# Drawing_binary_decimal_converter.net
KiCad netlist of a schematic drawn in EAGLE
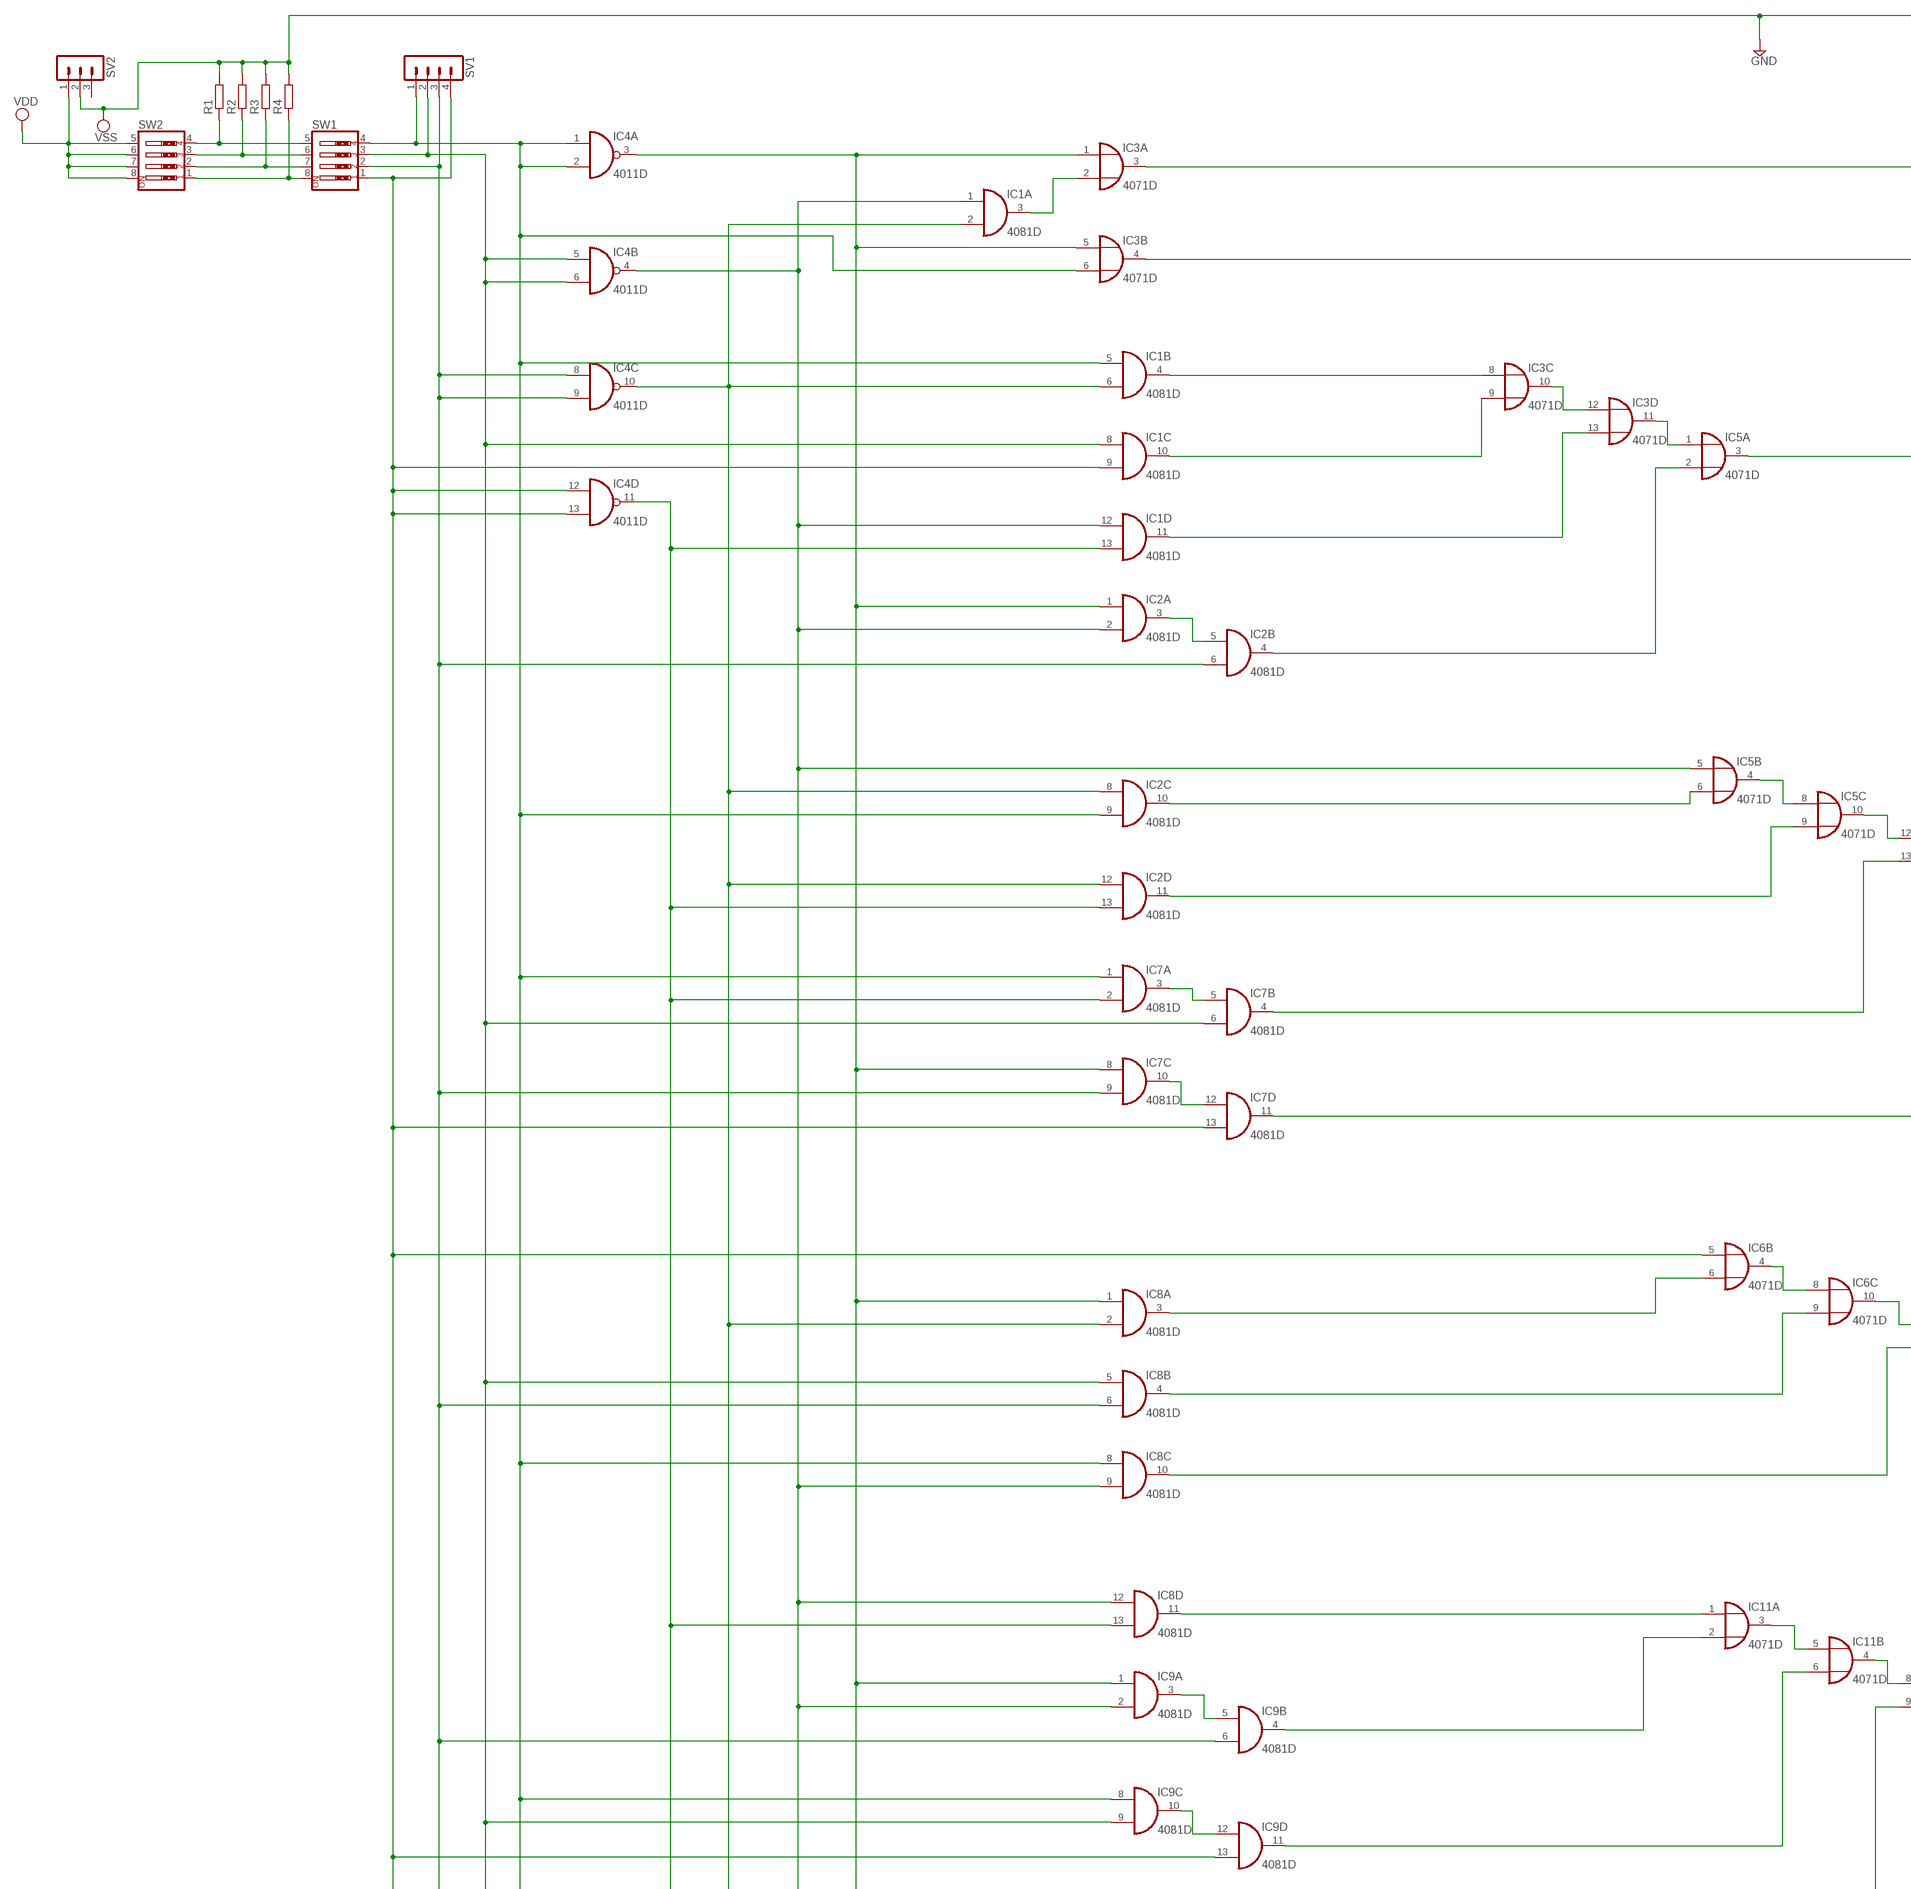
[diagram p0: schematic, sheet 1, part 1 of 3]
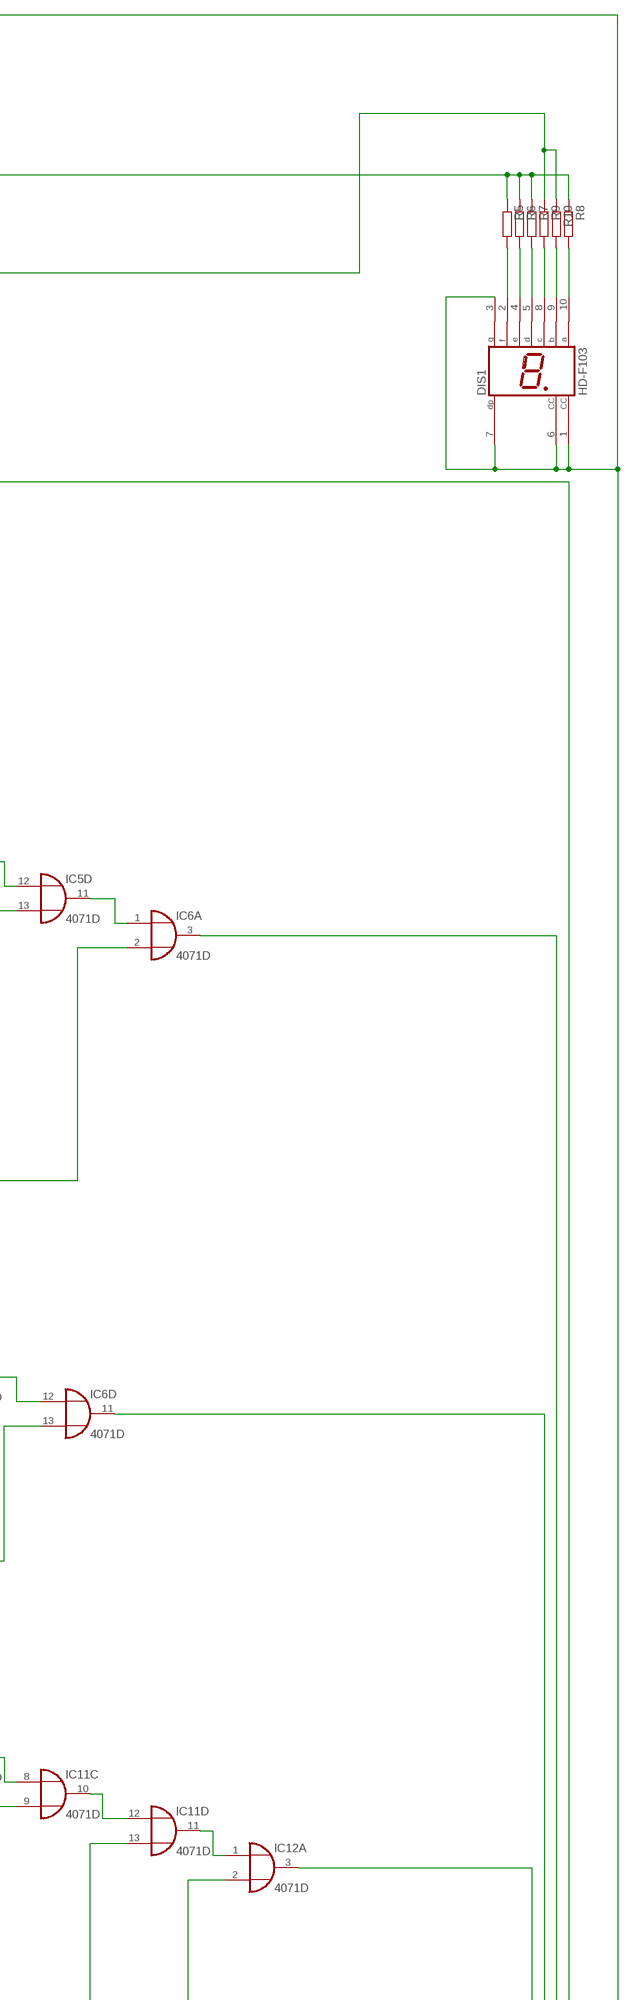
[diagram p1: schematic, sheet 1, part 2 of 3]
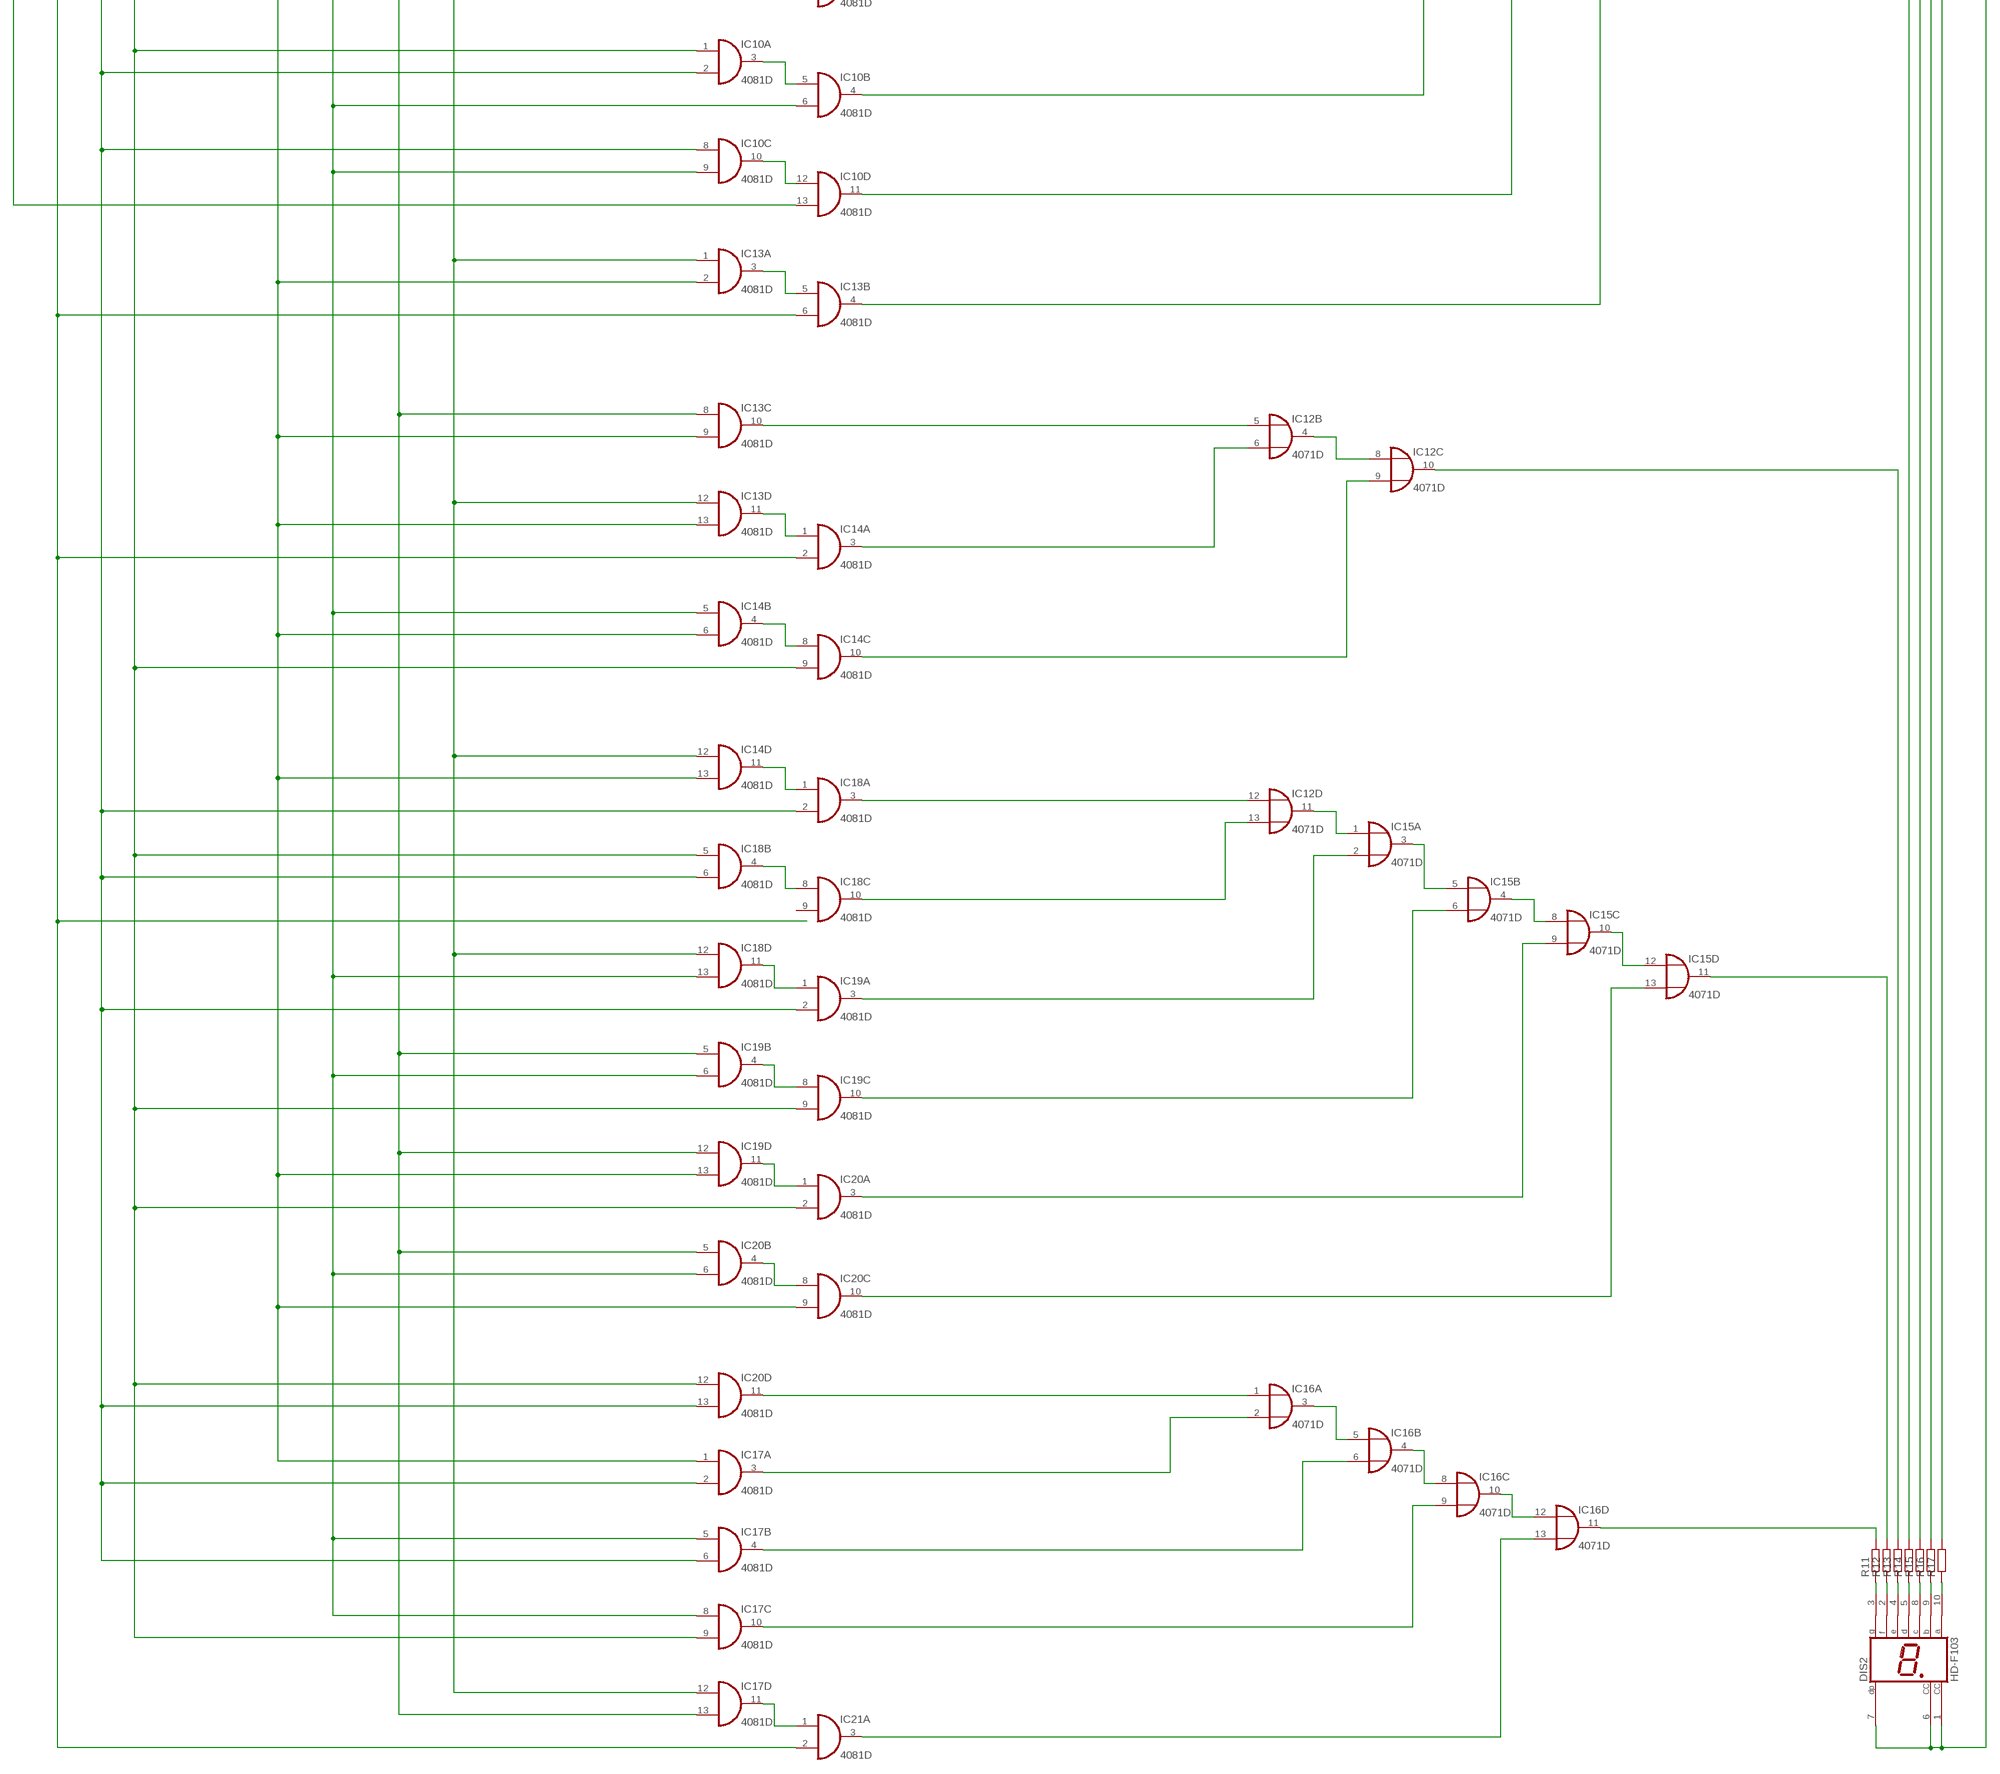
[diagram p2: schematic, sheet 1, part 3 of 3]

(export (version "E")
  (design (tool "Eeschema 10.0.6"))
  (components
    (comp (ref "DIS1")
      (value "HD-F103")
      (footprint "eagle-import:HDSP-E")
      (libsource (lib "eagle-import") (part "HD-F103"))
    )
    (comp (ref "DIS2")
      (value "HD-F103")
      (footprint "eagle-import:HDSP-E")
      (libsource (lib "eagle-import") (part "HD-F103"))
    )
    (comp (ref "IC1")
      (value "4081D")
      (footprint "eagle-import:SO14")
      (libsource (lib "eagle-import") (part "4081D"))
    )
    (comp (ref "IC2")
      (value "4081D")
      (footprint "eagle-import:SO14")
      (libsource (lib "eagle-import") (part "4081D"))
    )
    (comp (ref "IC3")
      (value "4071D")
      (footprint "eagle-import:SO14")
      (libsource (lib "eagle-import") (part "4071D"))
    )
    (comp (ref "IC4")
      (value "4011D")
      (footprint "eagle-import:SO14")
      (libsource (lib "eagle-import") (part "4011D"))
    )
    (comp (ref "IC5")
      (value "4071D")
      (footprint "eagle-import:SO14")
      (libsource (lib "eagle-import") (part "4071D"))
    )
    (comp (ref "IC6")
      (value "4071D")
      (footprint "eagle-import:SO14")
      (libsource (lib "eagle-import") (part "4071D"))
    )
    (comp (ref "IC7")
      (value "4081D")
      (footprint "eagle-import:SO14")
      (libsource (lib "eagle-import") (part "4081D"))
    )
    (comp (ref "IC8")
      (value "4081D")
      (footprint "eagle-import:SO14")
      (libsource (lib "eagle-import") (part "4081D"))
    )
    (comp (ref "IC9")
      (value "4081D")
      (footprint "eagle-import:SO14")
      (libsource (lib "eagle-import") (part "4081D"))
    )
    (comp (ref "IC10")
      (value "4081D")
      (footprint "eagle-import:SO14")
      (libsource (lib "eagle-import") (part "4081D"))
    )
    (comp (ref "IC11")
      (value "4071D")
      (footprint "eagle-import:SO14")
      (libsource (lib "eagle-import") (part "4071D"))
    )
    (comp (ref "IC12")
      (value "4071D")
      (footprint "eagle-import:SO14")
      (libsource (lib "eagle-import") (part "4071D"))
    )
    (comp (ref "IC13")
      (value "4081D")
      (footprint "eagle-import:SO14")
      (libsource (lib "eagle-import") (part "4081D"))
    )
    (comp (ref "IC14")
      (value "4081D")
      (footprint "eagle-import:SO14")
      (libsource (lib "eagle-import") (part "4081D"))
    )
    (comp (ref "IC15")
      (value "4071D")
      (footprint "eagle-import:SO14")
      (libsource (lib "eagle-import") (part "4071D"))
    )
    (comp (ref "IC16")
      (value "4071D")
      (footprint "eagle-import:SO14")
      (libsource (lib "eagle-import") (part "4071D"))
    )
    (comp (ref "IC17")
      (value "4081D")
      (footprint "eagle-import:SO14")
      (libsource (lib "eagle-import") (part "4081D"))
    )
    (comp (ref "IC18")
      (value "4081D")
      (footprint "eagle-import:SO14")
      (libsource (lib "eagle-import") (part "4081D"))
    )
    (comp (ref "IC19")
      (value "4081D")
      (footprint "eagle-import:SO14")
      (libsource (lib "eagle-import") (part "4081D"))
    )
    (comp (ref "IC20")
      (value "4081D")
      (footprint "eagle-import:SO14")
      (libsource (lib "eagle-import") (part "4081D"))
    )
    (comp (ref "IC21")
      (value "4081D")
      (footprint "eagle-import:SO14")
      (libsource (lib "eagle-import") (part "4081D"))
    )
    (comp (ref "R1")
      (value "R-EU_R1206")
      (footprint "eagle-import:R1206")
      (libsource (lib "eagle-import") (part "R-EU_R1206"))
    )
    (comp (ref "R2")
      (value "R-EU_R1206")
      (footprint "eagle-import:R1206")
      (libsource (lib "eagle-import") (part "R-EU_R1206"))
    )
    (comp (ref "R3")
      (value "R-EU_R1206")
      (footprint "eagle-import:R1206")
      (libsource (lib "eagle-import") (part "R-EU_R1206"))
    )
    (comp (ref "R4")
      (value "R-EU_R1206")
      (footprint "eagle-import:R1206")
      (libsource (lib "eagle-import") (part "R-EU_R1206"))
    )
    (comp (ref "R5")
      (value "R-EU_R1206")
      (footprint "eagle-import:R1206")
      (libsource (lib "eagle-import") (part "R-EU_R1206"))
    )
    (comp (ref "R6")
      (value "R-EU_R1206")
      (footprint "eagle-import:R1206")
      (libsource (lib "eagle-import") (part "R-EU_R1206"))
    )
    (comp (ref "R7")
      (value "R-EU_R1206")
      (footprint "eagle-import:R1206")
      (libsource (lib "eagle-import") (part "R-EU_R1206"))
    )
    (comp (ref "R8")
      (value "R-EU_R1206")
      (footprint "eagle-import:R1206")
      (libsource (lib "eagle-import") (part "R-EU_R1206"))
    )
    (comp (ref "R9")
      (value "R-EU_R1206")
      (footprint "eagle-import:R1206")
      (libsource (lib "eagle-import") (part "R-EU_R1206"))
    )
    (comp (ref "R10")
      (value "R-EU_R1206")
      (footprint "eagle-import:R1206")
      (libsource (lib "eagle-import") (part "R-EU_R1206"))
    )
    (comp (ref "R11")
      (value "R-EU_R1206")
      (footprint "eagle-import:R1206")
      (libsource (lib "eagle-import") (part "R-EU_R1206"))
    )
    (comp (ref "R12")
      (value "R-EU_R1206")
      (footprint "eagle-import:R1206")
      (libsource (lib "eagle-import") (part "R-EU_R1206"))
    )
    (comp (ref "R13")
      (value "R-EU_R1206")
      (footprint "eagle-import:R1206")
      (libsource (lib "eagle-import") (part "R-EU_R1206"))
    )
    (comp (ref "R14")
      (value "R-EU_R1206")
      (footprint "eagle-import:R1206")
      (libsource (lib "eagle-import") (part "R-EU_R1206"))
    )
    (comp (ref "R15")
      (value "R-EU_R1206")
      (footprint "eagle-import:R1206")
      (libsource (lib "eagle-import") (part "R-EU_R1206"))
    )
    (comp (ref "R16")
      (value "R-EU_R1206")
      (footprint "eagle-import:R1206")
      (libsource (lib "eagle-import") (part "R-EU_R1206"))
    )
    (comp (ref "R17")
      (value "R-EU_R1206")
      (footprint "eagle-import:R1206")
      (libsource (lib "eagle-import") (part "R-EU_R1206"))
    )
    (comp (ref "SV1")
      (value "MA04-1")
      (footprint "eagle-import:MA04-1")
      (libsource (lib "eagle-import") (part "MA04-1"))
    )
    (comp (ref "SV2")
      (value "MA03-1")
      (footprint "eagle-import:MA03-1")
      (libsource (lib "eagle-import") (part "MA03-1"))
    )
    (comp (ref "SW1")
      (value "SW_DIP-4")
      (footprint "eagle-import:EDG-04")
      (libsource (lib "eagle-import") (part "SW_DIP-4"))
    )
    (comp (ref "SW2")
      (value "SW_DIP-4")
      (footprint "eagle-import:EDG-04")
      (libsource (lib "eagle-import") (part "SW_DIP-4"))
    )
  )
  (nets
    (net (code "1") (name "GND") (class "Default")
      (node (ref "DIS1") (pin "1") (pinfunction "CC_1") (pintype "passive"))
      (node (ref "DIS1") (pin "3") (pinfunction "G_3") (pintype "passive"))
      (node (ref "DIS1") (pin "6") (pinfunction "CC_6") (pintype "passive"))
      (node (ref "DIS1") (pin "7") (pinfunction "DP_7") (pintype "passive"))
      (node (ref "DIS2") (pin "1") (pinfunction "CC_1") (pintype "passive"))
      (node (ref "DIS2") (pin "6") (pinfunction "CC_6") (pintype "passive"))
      (node (ref "DIS2") (pin "7") (pinfunction "DP_7") (pintype "passive"))
      (node (ref "R1") (pin "2") (pinfunction "2_2") (pintype "passive"))
      (node (ref "R2") (pin "2") (pinfunction "2_2") (pintype "passive"))
      (node (ref "R3") (pin "2") (pinfunction "2_2") (pintype "passive"))
      (node (ref "R4") (pin "2") (pinfunction "2_2") (pintype "passive"))
      (node (ref "SV2") (pin "2") (pinfunction "2_2") (pintype "passive"))
    )
    (net (code "2") (name "Net-(DIS1-A)") (class "Default")
      (node (ref "DIS1") (pin "10") (pinfunction "A_10") (pintype "passive"))
      (node (ref "R8") (pin "2") (pinfunction "2_2") (pintype "passive"))
    )
    (net (code "3") (name "Net-(DIS1-B)") (class "Default")
      (node (ref "DIS1") (pin "9") (pinfunction "B_9") (pintype "passive"))
      (node (ref "R10") (pin "2") (pinfunction "2_2") (pintype "passive"))
    )
    (net (code "4") (name "Net-(DIS1-C)") (class "Default")
      (node (ref "DIS1") (pin "8") (pinfunction "C_8") (pintype "passive"))
      (node (ref "R9") (pin "2") (pinfunction "2_2") (pintype "passive"))
    )
    (net (code "5") (name "Net-(DIS1-D)") (class "Default")
      (node (ref "DIS1") (pin "5") (pinfunction "D_5") (pintype "passive"))
      (node (ref "R7") (pin "2") (pinfunction "2_2") (pintype "passive"))
    )
    (net (code "6") (name "Net-(DIS1-E)") (class "Default")
      (node (ref "DIS1") (pin "4") (pinfunction "E_4") (pintype "passive"))
      (node (ref "R6") (pin "2") (pinfunction "2_2") (pintype "passive"))
    )
    (net (code "7") (name "Net-(DIS1-F)") (class "Default")
      (node (ref "DIS1") (pin "2") (pinfunction "F_2") (pintype "passive"))
      (node (ref "R5") (pin "2") (pinfunction "2_2") (pintype "passive"))
    )
    (net (code "8") (name "Net-(DIS2-A)") (class "Default")
      (node (ref "DIS2") (pin "10") (pinfunction "A_10") (pintype "passive"))
      (node (ref "R17") (pin "1") (pinfunction "1_1") (pintype "passive"))
    )
    (net (code "9") (name "Net-(DIS2-B)") (class "Default")
      (node (ref "DIS2") (pin "9") (pinfunction "B_9") (pintype "passive"))
      (node (ref "R16") (pin "1") (pinfunction "1_1") (pintype "passive"))
    )
    (net (code "10") (name "Net-(DIS2-C)") (class "Default")
      (node (ref "DIS2") (pin "8") (pinfunction "C_8") (pintype "passive"))
      (node (ref "R15") (pin "1") (pinfunction "1_1") (pintype "passive"))
    )
    (net (code "11") (name "Net-(DIS2-D)") (class "Default")
      (node (ref "DIS2") (pin "5") (pinfunction "D_5") (pintype "passive"))
      (node (ref "R14") (pin "1") (pinfunction "1_1") (pintype "passive"))
    )
    (net (code "12") (name "Net-(DIS2-E)") (class "Default")
      (node (ref "DIS2") (pin "4") (pinfunction "E_4") (pintype "passive"))
      (node (ref "R13") (pin "1") (pinfunction "1_1") (pintype "passive"))
    )
    (net (code "13") (name "Net-(DIS2-F)") (class "Default")
      (node (ref "DIS2") (pin "2") (pinfunction "F_2") (pintype "passive"))
      (node (ref "R12") (pin "1") (pinfunction "1_1") (pintype "passive"))
    )
    (net (code "14") (name "Net-(DIS2-G)") (class "Default")
      (node (ref "DIS2") (pin "3") (pinfunction "G_3") (pintype "passive"))
      (node (ref "R11") (pin "1") (pinfunction "1_1") (pintype "passive"))
    )
    (net (code "15") (name "Net-(IC1A-O)") (class "Default")
      (node (ref "IC1") (pin "3") (pinfunction "O_3") (pintype "output"))
      (node (ref "IC3") (pin "2") (pinfunction "I1_2") (pintype "input"))
    )
    (net (code "16") (name "Net-(IC1B-O)") (class "Default")
      (node (ref "IC1") (pin "4") (pinfunction "O_4") (pintype "output"))
      (node (ref "IC3") (pin "8") (pinfunction "I0_8") (pintype "input"))
    )
    (net (code "17") (name "Net-(IC1C-O)") (class "Default")
      (node (ref "IC1") (pin "10") (pinfunction "O_10") (pintype "output"))
      (node (ref "IC3") (pin "9") (pinfunction "I1_9") (pintype "input"))
    )
    (net (code "18") (name "Net-(IC1D-O)") (class "Default")
      (node (ref "IC1") (pin "11") (pinfunction "O_11") (pintype "output"))
      (node (ref "IC3") (pin "13") (pinfunction "I1_13") (pintype "input"))
    )
    (net (code "19") (name "Net-(IC2A-O)") (class "Default")
      (node (ref "IC2") (pin "3") (pinfunction "O_3") (pintype "output"))
      (node (ref "IC2") (pin "5") (pinfunction "I0_5") (pintype "input"))
    )
    (net (code "20") (name "Net-(IC2B-O)") (class "Default")
      (node (ref "IC2") (pin "4") (pinfunction "O_4") (pintype "output"))
      (node (ref "IC5") (pin "2") (pinfunction "I1_2") (pintype "input"))
    )
    (net (code "21") (name "Net-(IC2C-O)") (class "Default")
      (node (ref "IC2") (pin "10") (pinfunction "O_10") (pintype "output"))
      (node (ref "IC5") (pin "6") (pinfunction "I1_6") (pintype "input"))
    )
    (net (code "22") (name "Net-(IC2D-O)") (class "Default")
      (node (ref "IC2") (pin "11") (pinfunction "O_11") (pintype "output"))
      (node (ref "IC5") (pin "9") (pinfunction "I1_9") (pintype "input"))
    )
    (net (code "23") (name "Net-(IC3A-O)") (class "Default")
      (node (ref "IC3") (pin "3") (pinfunction "O_3") (pintype "output"))
      (node (ref "R5") (pin "1") (pinfunction "1_1") (pintype "passive"))
      (node (ref "R6") (pin "1") (pinfunction "1_1") (pintype "passive"))
      (node (ref "R7") (pin "1") (pinfunction "1_1") (pintype "passive"))
      (node (ref "R8") (pin "1") (pinfunction "1_1") (pintype "passive"))
    )
    (net (code "24") (name "Net-(IC3B-O)") (class "Default")
      (node (ref "IC3") (pin "4") (pinfunction "O_4") (pintype "output"))
      (node (ref "R10") (pin "1") (pinfunction "1_1") (pintype "passive"))
      (node (ref "R9") (pin "1") (pinfunction "1_1") (pintype "passive"))
    )
    (net (code "25") (name "Net-(IC3C-O)") (class "Default")
      (node (ref "IC3") (pin "10") (pinfunction "O_10") (pintype "output"))
      (node (ref "IC3") (pin "12") (pinfunction "I0_12") (pintype "input"))
    )
    (net (code "26") (name "Net-(IC3D-O)") (class "Default")
      (node (ref "IC3") (pin "11") (pinfunction "O_11") (pintype "output"))
      (node (ref "IC5") (pin "1") (pinfunction "I0_1") (pintype "input"))
    )
    (net (code "27") (name "Net-(IC5A-O)") (class "Default")
      (node (ref "IC5") (pin "3") (pinfunction "O_3") (pintype "output"))
      (node (ref "R17") (pin "2") (pinfunction "2_2") (pintype "passive"))
    )
    (net (code "28") (name "Net-(IC5B-O)") (class "Default")
      (node (ref "IC5") (pin "4") (pinfunction "O_4") (pintype "output"))
      (node (ref "IC5") (pin "8") (pinfunction "I0_8") (pintype "input"))
    )
    (net (code "29") (name "Net-(IC5C-O)") (class "Default")
      (node (ref "IC5") (pin "10") (pinfunction "O_10") (pintype "output"))
      (node (ref "IC5") (pin "12") (pinfunction "I0_12") (pintype "input"))
    )
    (net (code "30") (name "Net-(IC5D-I1)") (class "Default")
      (node (ref "IC5") (pin "13") (pinfunction "I1_13") (pintype "input"))
      (node (ref "IC7") (pin "4") (pinfunction "O_4") (pintype "output"))
    )
    (net (code "31") (name "Net-(IC5D-O)") (class "Default")
      (node (ref "IC5") (pin "11") (pinfunction "O_11") (pintype "output"))
      (node (ref "IC6") (pin "1") (pinfunction "I0_1") (pintype "input"))
    )
    (net (code "32") (name "Net-(IC6A-I1)") (class "Default")
      (node (ref "IC6") (pin "2") (pinfunction "I1_2") (pintype "input"))
      (node (ref "IC7") (pin "11") (pinfunction "O_11") (pintype "output"))
    )
    (net (code "33") (name "Net-(IC6A-O)") (class "Default")
      (node (ref "IC6") (pin "3") (pinfunction "O_3") (pintype "output"))
      (node (ref "R16") (pin "2") (pinfunction "2_2") (pintype "passive"))
    )
    (net (code "34") (name "Net-(IC6B-I1)") (class "Default")
      (node (ref "IC6") (pin "6") (pinfunction "I1_6") (pintype "input"))
      (node (ref "IC8") (pin "3") (pinfunction "O_3") (pintype "output"))
    )
    (net (code "35") (name "Net-(IC6B-O)") (class "Default")
      (node (ref "IC6") (pin "4") (pinfunction "O_4") (pintype "output"))
      (node (ref "IC6") (pin "8") (pinfunction "I0_8") (pintype "input"))
    )
    (net (code "36") (name "Net-(IC6C-I1)") (class "Default")
      (node (ref "IC6") (pin "9") (pinfunction "I1_9") (pintype "input"))
      (node (ref "IC8") (pin "4") (pinfunction "O_4") (pintype "output"))
    )
    (net (code "37") (name "Net-(IC6C-O)") (class "Default")
      (node (ref "IC6") (pin "10") (pinfunction "O_10") (pintype "output"))
      (node (ref "IC6") (pin "12") (pinfunction "I0_12") (pintype "input"))
    )
    (net (code "38") (name "Net-(IC6D-I1)") (class "Default")
      (node (ref "IC6") (pin "13") (pinfunction "I1_13") (pintype "input"))
      (node (ref "IC8") (pin "10") (pinfunction "O_10") (pintype "output"))
    )
    (net (code "39") (name "Net-(IC6D-O)") (class "Default")
      (node (ref "IC6") (pin "11") (pinfunction "O_11") (pintype "output"))
      (node (ref "R15") (pin "2") (pinfunction "2_2") (pintype "passive"))
    )
    (net (code "40") (name "Net-(IC7A-O)") (class "Default")
      (node (ref "IC7") (pin "3") (pinfunction "O_3") (pintype "output"))
      (node (ref "IC7") (pin "5") (pinfunction "I0_5") (pintype "input"))
    )
    (net (code "41") (name "Net-(IC7C-O)") (class "Default")
      (node (ref "IC7") (pin "10") (pinfunction "O_10") (pintype "output"))
      (node (ref "IC7") (pin "12") (pinfunction "I0_12") (pintype "input"))
    )
    (net (code "42") (name "Net-(IC9A-O)") (class "Default")
      (node (ref "IC9") (pin "3") (pinfunction "O_3") (pintype "output"))
      (node (ref "IC9") (pin "5") (pinfunction "I0_5") (pintype "input"))
    )
    (net (code "43") (name "Net-(IC9C-O)") (class "Default")
      (node (ref "IC9") (pin "10") (pinfunction "O_10") (pintype "output"))
      (node (ref "IC9") (pin "12") (pinfunction "I0_12") (pintype "input"))
    )
    (net (code "44") (name "Net-(IC10A-I0)") (class "Default")
      (node (ref "IC1") (pin "5") (pinfunction "I0_5") (pintype "input"))
      (node (ref "IC10") (pin "1") (pinfunction "I0_1") (pintype "input"))
      (node (ref "IC14") (pin "9") (pinfunction "I1_9") (pintype "input"))
      (node (ref "IC17") (pin "9") (pinfunction "I1_9") (pintype "input"))
      (node (ref "IC18") (pin "5") (pinfunction "I0_5") (pintype "input"))
      (node (ref "IC19") (pin "9") (pinfunction "I1_9") (pintype "input"))
      (node (ref "IC2") (pin "9") (pinfunction "I1_9") (pintype "input"))
      (node (ref "IC20") (pin "12") (pinfunction "I0_12") (pintype "input"))
      (node (ref "IC20") (pin "2") (pinfunction "I1_2") (pintype "input"))
      (node (ref "IC3") (pin "6") (pinfunction "I1_6") (pintype "input"))
      (node (ref "IC4") (pin "1") (pinfunction "I0_1") (pintype "input"))
      (node (ref "IC4") (pin "2") (pinfunction "I1_2") (pintype "input"))
      (node (ref "IC7") (pin "1") (pinfunction "I0_1") (pintype "input"))
      (node (ref "IC8") (pin "8") (pinfunction "I0_8") (pintype "input"))
      (node (ref "IC9") (pin "8") (pinfunction "I0_8") (pintype "input"))
      (node (ref "SV1") (pin "1") (pinfunction "1_1") (pintype "passive"))
      (node (ref "SW1") (pin "4") (pinfunction "4_4") (pintype "passive"))
    )
    (net (code "45") (name "Net-(IC10A-I1)") (class "Default")
      (node (ref "IC1") (pin "8") (pinfunction "I0_8") (pintype "input"))
      (node (ref "IC10") (pin "2") (pinfunction "I1_2") (pintype "input"))
      (node (ref "IC10") (pin "8") (pinfunction "I0_8") (pintype "input"))
      (node (ref "IC17") (pin "2") (pinfunction "I1_2") (pintype "input"))
      (node (ref "IC17") (pin "6") (pinfunction "I1_6") (pintype "input"))
      (node (ref "IC18") (pin "2") (pinfunction "I1_2") (pintype "input"))
      (node (ref "IC18") (pin "6") (pinfunction "I1_6") (pintype "input"))
      (node (ref "IC19") (pin "2") (pinfunction "I1_2") (pintype "input"))
      (node (ref "IC20") (pin "13") (pinfunction "I1_13") (pintype "input"))
      (node (ref "IC4") (pin "5") (pinfunction "I0_5") (pintype "input"))
      (node (ref "IC4") (pin "6") (pinfunction "I1_6") (pintype "input"))
      (node (ref "IC7") (pin "6") (pinfunction "I1_6") (pintype "input"))
      (node (ref "IC8") (pin "5") (pinfunction "I0_5") (pintype "input"))
      (node (ref "IC9") (pin "9") (pinfunction "I1_9") (pintype "input"))
      (node (ref "SV1") (pin "2") (pinfunction "2_2") (pintype "passive"))
      (node (ref "SW1") (pin "3") (pinfunction "3_3") (pintype "passive"))
    )
    (net (code "46") (name "Net-(IC10A-O)") (class "Default")
      (node (ref "IC10") (pin "3") (pinfunction "O_3") (pintype "output"))
      (node (ref "IC10") (pin "5") (pinfunction "I0_5") (pintype "input"))
    )
    (net (code "47") (name "Net-(IC10B-I1)") (class "Default")
      (node (ref "IC1") (pin "2") (pinfunction "I1_2") (pintype "input"))
      (node (ref "IC1") (pin "6") (pinfunction "I1_6") (pintype "input"))
      (node (ref "IC10") (pin "6") (pinfunction "I1_6") (pintype "input"))
      (node (ref "IC10") (pin "9") (pinfunction "I1_9") (pintype "input"))
      (node (ref "IC14") (pin "5") (pinfunction "I0_5") (pintype "input"))
      (node (ref "IC17") (pin "5") (pinfunction "I0_5") (pintype "input"))
      (node (ref "IC17") (pin "8") (pinfunction "I0_8") (pintype "input"))
      (node (ref "IC18") (pin "13") (pinfunction "I1_13") (pintype "input"))
      (node (ref "IC19") (pin "6") (pinfunction "I1_6") (pintype "input"))
      (node (ref "IC2") (pin "12") (pinfunction "I0_12") (pintype "input"))
      (node (ref "IC2") (pin "8") (pinfunction "I0_8") (pintype "input"))
      (node (ref "IC20") (pin "6") (pinfunction "I1_6") (pintype "input"))
      (node (ref "IC4") (pin "10") (pinfunction "O_10") (pintype "output"))
      (node (ref "IC8") (pin "2") (pinfunction "I1_2") (pintype "input"))
    )
    (net (code "48") (name "Net-(IC10B-O)") (class "Default")
      (node (ref "IC10") (pin "4") (pinfunction "O_4") (pintype "output"))
      (node (ref "IC11") (pin "9") (pinfunction "I1_9") (pintype "input"))
    )
    (net (code "49") (name "Net-(IC10C-O)") (class "Default")
      (node (ref "IC10") (pin "10") (pinfunction "O_10") (pintype "output"))
      (node (ref "IC10") (pin "12") (pinfunction "I0_12") (pintype "input"))
    )
    (net (code "50") (name "Net-(IC10D-I1)") (class "Default")
      (node (ref "IC1") (pin "9") (pinfunction "I1_9") (pintype "input"))
      (node (ref "IC10") (pin "13") (pinfunction "I1_13") (pintype "input"))
      (node (ref "IC4") (pin "12") (pinfunction "I0_12") (pintype "input"))
      (node (ref "IC4") (pin "13") (pinfunction "I1_13") (pintype "input"))
      (node (ref "IC6") (pin "5") (pinfunction "I0_5") (pintype "input"))
      (node (ref "IC7") (pin "13") (pinfunction "I1_13") (pintype "input"))
      (node (ref "IC9") (pin "13") (pinfunction "I1_13") (pintype "input"))
      (node (ref "SV1") (pin "4") (pinfunction "4_4") (pintype "passive"))
      (node (ref "SW1") (pin "1") (pinfunction "1_1") (pintype "passive"))
    )
    (net (code "51") (name "Net-(IC10D-O)") (class "Default")
      (node (ref "IC10") (pin "11") (pinfunction "O_11") (pintype "output"))
      (node (ref "IC11") (pin "13") (pinfunction "I1_13") (pintype "input"))
    )
    (net (code "52") (name "Net-(IC11A-I0)") (class "Default")
      (node (ref "IC11") (pin "1") (pinfunction "I0_1") (pintype "input"))
      (node (ref "IC8") (pin "11") (pinfunction "O_11") (pintype "output"))
    )
    (net (code "53") (name "Net-(IC11A-I1)") (class "Default")
      (node (ref "IC11") (pin "2") (pinfunction "I1_2") (pintype "input"))
      (node (ref "IC9") (pin "4") (pinfunction "O_4") (pintype "output"))
    )
    (net (code "54") (name "Net-(IC11A-O)") (class "Default")
      (node (ref "IC11") (pin "3") (pinfunction "O_3") (pintype "output"))
      (node (ref "IC11") (pin "5") (pinfunction "I0_5") (pintype "input"))
    )
    (net (code "55") (name "Net-(IC11B-I1)") (class "Default")
      (node (ref "IC11") (pin "6") (pinfunction "I1_6") (pintype "input"))
      (node (ref "IC9") (pin "11") (pinfunction "O_11") (pintype "output"))
    )
    (net (code "56") (name "Net-(IC11B-O)") (class "Default")
      (node (ref "IC11") (pin "4") (pinfunction "O_4") (pintype "output"))
      (node (ref "IC11") (pin "8") (pinfunction "I0_8") (pintype "input"))
    )
    (net (code "57") (name "Net-(IC11C-O)") (class "Default")
      (node (ref "IC11") (pin "10") (pinfunction "O_10") (pintype "output"))
      (node (ref "IC11") (pin "12") (pinfunction "I0_12") (pintype "input"))
    )
    (net (code "58") (name "Net-(IC11D-O)") (class "Default")
      (node (ref "IC11") (pin "11") (pinfunction "O_11") (pintype "output"))
      (node (ref "IC12") (pin "1") (pinfunction "I0_1") (pintype "input"))
    )
    (net (code "59") (name "Net-(IC12A-I1)") (class "Default")
      (node (ref "IC12") (pin "2") (pinfunction "I1_2") (pintype "input"))
      (node (ref "IC13") (pin "4") (pinfunction "O_4") (pintype "output"))
    )
    (net (code "60") (name "Net-(IC12A-O)") (class "Default")
      (node (ref "IC12") (pin "3") (pinfunction "O_3") (pintype "output"))
      (node (ref "R14") (pin "2") (pinfunction "2_2") (pintype "passive"))
    )
    (net (code "61") (name "Net-(IC12B-I0)") (class "Default")
      (node (ref "IC12") (pin "5") (pinfunction "I0_5") (pintype "input"))
      (node (ref "IC13") (pin "10") (pinfunction "O_10") (pintype "output"))
    )
    (net (code "62") (name "Net-(IC12B-I1)") (class "Default")
      (node (ref "IC12") (pin "6") (pinfunction "I1_6") (pintype "input"))
      (node (ref "IC14") (pin "3") (pinfunction "O_3") (pintype "output"))
    )
    (net (code "63") (name "Net-(IC12B-O)") (class "Default")
      (node (ref "IC12") (pin "4") (pinfunction "O_4") (pintype "output"))
      (node (ref "IC12") (pin "8") (pinfunction "I0_8") (pintype "input"))
    )
    (net (code "64") (name "Net-(IC12C-I1)") (class "Default")
      (node (ref "IC12") (pin "9") (pinfunction "I1_9") (pintype "input"))
      (node (ref "IC14") (pin "10") (pinfunction "O_10") (pintype "output"))
    )
    (net (code "65") (name "Net-(IC12C-O)") (class "Default")
      (node (ref "IC12") (pin "10") (pinfunction "O_10") (pintype "output"))
      (node (ref "R13") (pin "2") (pinfunction "2_2") (pintype "passive"))
    )
    (net (code "66") (name "Net-(IC12D-I0)") (class "Default")
      (node (ref "IC12") (pin "12") (pinfunction "I0_12") (pintype "input"))
      (node (ref "IC18") (pin "3") (pinfunction "O_3") (pintype "output"))
    )
    (net (code "67") (name "Net-(IC12D-I1)") (class "Default")
      (node (ref "IC12") (pin "13") (pinfunction "I1_13") (pintype "input"))
      (node (ref "IC18") (pin "10") (pinfunction "O_10") (pintype "output"))
    )
    (net (code "68") (name "Net-(IC12D-O)") (class "Default")
      (node (ref "IC12") (pin "11") (pinfunction "O_11") (pintype "output"))
      (node (ref "IC15") (pin "1") (pinfunction "I0_1") (pintype "input"))
    )
    (net (code "69") (name "Net-(IC13A-I0)") (class "Default")
      (node (ref "IC13") (pin "1") (pinfunction "I0_1") (pintype "input"))
      (node (ref "IC13") (pin "12") (pinfunction "I0_12") (pintype "input"))
      (node (ref "IC14") (pin "12") (pinfunction "I0_12") (pintype "input"))
      (node (ref "IC17") (pin "12") (pinfunction "I0_12") (pintype "input"))
      (node (ref "IC18") (pin "12") (pinfunction "I0_12") (pintype "input"))
      (node (ref "IC2") (pin "1") (pinfunction "I0_1") (pintype "input"))
      (node (ref "IC3") (pin "1") (pinfunction "I0_1") (pintype "input"))
      (node (ref "IC3") (pin "5") (pinfunction "I0_5") (pintype "input"))
      (node (ref "IC4") (pin "3") (pinfunction "O_3") (pintype "output"))
      (node (ref "IC7") (pin "8") (pinfunction "I0_8") (pintype "input"))
      (node (ref "IC8") (pin "1") (pinfunction "I0_1") (pintype "input"))
      (node (ref "IC9") (pin "1") (pinfunction "I0_1") (pintype "input"))
    )
    (net (code "70") (name "Net-(IC13A-I1)") (class "Default")
      (node (ref "IC1") (pin "13") (pinfunction "I1_13") (pintype "input"))
      (node (ref "IC13") (pin "13") (pinfunction "I1_13") (pintype "input"))
      (node (ref "IC13") (pin "2") (pinfunction "I1_2") (pintype "input"))
      (node (ref "IC13") (pin "9") (pinfunction "I1_9") (pintype "input"))
      (node (ref "IC14") (pin "13") (pinfunction "I1_13") (pintype "input"))
      (node (ref "IC14") (pin "6") (pinfunction "I1_6") (pintype "input"))
      (node (ref "IC17") (pin "1") (pinfunction "I0_1") (pintype "input"))
      (node (ref "IC19") (pin "13") (pinfunction "I1_13") (pintype "input"))
      (node (ref "IC2") (pin "13") (pinfunction "I1_13") (pintype "input"))
      (node (ref "IC20") (pin "9") (pinfunction "I1_9") (pintype "input"))
      (node (ref "IC4") (pin "11") (pinfunction "O_11") (pintype "output"))
      (node (ref "IC7") (pin "2") (pinfunction "I1_2") (pintype "input"))
      (node (ref "IC8") (pin "13") (pinfunction "I1_13") (pintype "input"))
    )
    (net (code "71") (name "Net-(IC13A-O)") (class "Default")
      (node (ref "IC13") (pin "3") (pinfunction "O_3") (pintype "output"))
      (node (ref "IC13") (pin "5") (pinfunction "I0_5") (pintype "input"))
    )
    (net (code "72") (name "Net-(IC13B-I1)") (class "Default")
      (node (ref "IC13") (pin "6") (pinfunction "I1_6") (pintype "input"))
      (node (ref "IC14") (pin "2") (pinfunction "I1_2") (pintype "input"))
      (node (ref "IC2") (pin "6") (pinfunction "I1_6") (pintype "input"))
      (node (ref "IC21") (pin "2") (pinfunction "I1_2") (pintype "input"))
      (node (ref "IC4") (pin "8") (pinfunction "I0_8") (pintype "input"))
      (node (ref "IC4") (pin "9") (pinfunction "I1_9") (pintype "input"))
      (node (ref "IC7") (pin "9") (pinfunction "I1_9") (pintype "input"))
      (node (ref "IC8") (pin "6") (pinfunction "I1_6") (pintype "input"))
      (node (ref "IC9") (pin "6") (pinfunction "I1_6") (pintype "input"))
      (node (ref "SV1") (pin "3") (pinfunction "3_3") (pintype "passive"))
      (node (ref "SW1") (pin "2") (pinfunction "2_2") (pintype "passive"))
    )
    (net (code "73") (name "Net-(IC13C-I0)") (class "Default")
      (node (ref "IC1") (pin "1") (pinfunction "I0_1") (pintype "input"))
      (node (ref "IC1") (pin "12") (pinfunction "I0_12") (pintype "input"))
      (node (ref "IC13") (pin "8") (pinfunction "I0_8") (pintype "input"))
      (node (ref "IC17") (pin "13") (pinfunction "I1_13") (pintype "input"))
      (node (ref "IC19") (pin "12") (pinfunction "I0_12") (pintype "input"))
      (node (ref "IC19") (pin "5") (pinfunction "I0_5") (pintype "input"))
      (node (ref "IC2") (pin "2") (pinfunction "I1_2") (pintype "input"))
      (node (ref "IC20") (pin "5") (pinfunction "I0_5") (pintype "input"))
      (node (ref "IC4") (pin "4") (pinfunction "O_4") (pintype "output"))
      (node (ref "IC5") (pin "5") (pinfunction "I0_5") (pintype "input"))
      (node (ref "IC8") (pin "12") (pinfunction "I0_12") (pintype "input"))
      (node (ref "IC8") (pin "9") (pinfunction "I1_9") (pintype "input"))
      (node (ref "IC9") (pin "2") (pinfunction "I1_2") (pintype "input"))
    )
    (net (code "74") (name "Net-(IC13D-O)") (class "Default")
      (node (ref "IC13") (pin "11") (pinfunction "O_11") (pintype "output"))
      (node (ref "IC14") (pin "1") (pinfunction "I0_1") (pintype "input"))
    )
    (net (code "75") (name "Net-(IC14B-O)") (class "Default")
      (node (ref "IC14") (pin "4") (pinfunction "O_4") (pintype "output"))
      (node (ref "IC14") (pin "8") (pinfunction "I0_8") (pintype "input"))
    )
    (net (code "76") (name "Net-(IC14D-O)") (class "Default")
      (node (ref "IC14") (pin "11") (pinfunction "O_11") (pintype "output"))
      (node (ref "IC18") (pin "1") (pinfunction "I0_1") (pintype "input"))
    )
    (net (code "77") (name "Net-(IC15A-I1)") (class "Default")
      (node (ref "IC15") (pin "2") (pinfunction "I1_2") (pintype "input"))
      (node (ref "IC19") (pin "3") (pinfunction "O_3") (pintype "output"))
    )
    (net (code "78") (name "Net-(IC15A-O)") (class "Default")
      (node (ref "IC15") (pin "3") (pinfunction "O_3") (pintype "output"))
      (node (ref "IC15") (pin "5") (pinfunction "I0_5") (pintype "input"))
    )
    (net (code "79") (name "Net-(IC15B-I1)") (class "Default")
      (node (ref "IC15") (pin "6") (pinfunction "I1_6") (pintype "input"))
      (node (ref "IC19") (pin "10") (pinfunction "O_10") (pintype "output"))
    )
    (net (code "80") (name "Net-(IC15B-O)") (class "Default")
      (node (ref "IC15") (pin "4") (pinfunction "O_4") (pintype "output"))
      (node (ref "IC15") (pin "8") (pinfunction "I0_8") (pintype "input"))
    )
    (net (code "81") (name "Net-(IC15C-I1)") (class "Default")
      (node (ref "IC15") (pin "9") (pinfunction "I1_9") (pintype "input"))
      (node (ref "IC20") (pin "3") (pinfunction "O_3") (pintype "output"))
    )
    (net (code "82") (name "Net-(IC15C-O)") (class "Default")
      (node (ref "IC15") (pin "10") (pinfunction "O_10") (pintype "output"))
      (node (ref "IC15") (pin "12") (pinfunction "I0_12") (pintype "input"))
    )
    (net (code "83") (name "Net-(IC15D-I1)") (class "Default")
      (node (ref "IC15") (pin "13") (pinfunction "I1_13") (pintype "input"))
      (node (ref "IC20") (pin "10") (pinfunction "O_10") (pintype "output"))
    )
    (net (code "84") (name "Net-(IC15D-O)") (class "Default")
      (node (ref "IC15") (pin "11") (pinfunction "O_11") (pintype "output"))
      (node (ref "R12") (pin "2") (pinfunction "2_2") (pintype "passive"))
    )
    (net (code "85") (name "Net-(IC16A-I0)") (class "Default")
      (node (ref "IC16") (pin "1") (pinfunction "I0_1") (pintype "input"))
      (node (ref "IC20") (pin "11") (pinfunction "O_11") (pintype "output"))
    )
    (net (code "86") (name "Net-(IC16A-I1)") (class "Default")
      (node (ref "IC16") (pin "2") (pinfunction "I1_2") (pintype "input"))
      (node (ref "IC17") (pin "3") (pinfunction "O_3") (pintype "output"))
    )
    (net (code "87") (name "Net-(IC16A-O)") (class "Default")
      (node (ref "IC16") (pin "3") (pinfunction "O_3") (pintype "output"))
      (node (ref "IC16") (pin "5") (pinfunction "I0_5") (pintype "input"))
    )
    (net (code "88") (name "Net-(IC16B-I1)") (class "Default")
      (node (ref "IC16") (pin "6") (pinfunction "I1_6") (pintype "input"))
      (node (ref "IC17") (pin "4") (pinfunction "O_4") (pintype "output"))
    )
    (net (code "89") (name "Net-(IC16B-O)") (class "Default")
      (node (ref "IC16") (pin "4") (pinfunction "O_4") (pintype "output"))
      (node (ref "IC16") (pin "8") (pinfunction "I0_8") (pintype "input"))
    )
    (net (code "90") (name "Net-(IC16C-I1)") (class "Default")
      (node (ref "IC16") (pin "9") (pinfunction "I1_9") (pintype "input"))
      (node (ref "IC17") (pin "10") (pinfunction "O_10") (pintype "output"))
    )
    (net (code "91") (name "Net-(IC16C-O)") (class "Default")
      (node (ref "IC16") (pin "10") (pinfunction "O_10") (pintype "output"))
      (node (ref "IC16") (pin "12") (pinfunction "I0_12") (pintype "input"))
    )
    (net (code "92") (name "Net-(IC16D-I1)") (class "Default")
      (node (ref "IC16") (pin "13") (pinfunction "I1_13") (pintype "input"))
      (node (ref "IC21") (pin "3") (pinfunction "O_3") (pintype "output"))
    )
    (net (code "93") (name "Net-(IC16D-O)") (class "Default")
      (node (ref "IC16") (pin "11") (pinfunction "O_11") (pintype "output"))
      (node (ref "R11") (pin "2") (pinfunction "2_2") (pintype "passive"))
    )
    (net (code "94") (name "Net-(IC17D-O)") (class "Default")
      (node (ref "IC17") (pin "11") (pinfunction "O_11") (pintype "output"))
      (node (ref "IC21") (pin "1") (pinfunction "I0_1") (pintype "input"))
    )
    (net (code "95") (name "Net-(IC18B-O)") (class "Default")
      (node (ref "IC18") (pin "4") (pinfunction "O_4") (pintype "output"))
      (node (ref "IC18") (pin "8") (pinfunction "I0_8") (pintype "input"))
    )
    (net (code "96") (name "Net-(IC18D-O)") (class "Default")
      (node (ref "IC18") (pin "11") (pinfunction "O_11") (pintype "output"))
      (node (ref "IC19") (pin "1") (pinfunction "I0_1") (pintype "input"))
    )
    (net (code "97") (name "Net-(IC19B-O)") (class "Default")
      (node (ref "IC19") (pin "4") (pinfunction "O_4") (pintype "output"))
      (node (ref "IC19") (pin "8") (pinfunction "I0_8") (pintype "input"))
    )
    (net (code "98") (name "Net-(IC19D-O)") (class "Default")
      (node (ref "IC19") (pin "11") (pinfunction "O_11") (pintype "output"))
      (node (ref "IC20") (pin "1") (pinfunction "I0_1") (pintype "input"))
    )
    (net (code "99") (name "Net-(IC20B-O)") (class "Default")
      (node (ref "IC20") (pin "4") (pinfunction "O_4") (pintype "output"))
      (node (ref "IC20") (pin "8") (pinfunction "I0_8") (pintype "input"))
    )
    (net (code "100") (name "Net-(R1-Pad1)") (class "Default")
      (node (ref "R1") (pin "1") (pinfunction "1_1") (pintype "passive"))
      (node (ref "SW1") (pin "5") (pinfunction "5_5") (pintype "passive"))
      (node (ref "SW2") (pin "4") (pinfunction "4_4") (pintype "passive"))
    )
    (net (code "101") (name "Net-(R2-Pad1)") (class "Default")
      (node (ref "R2") (pin "1") (pinfunction "1_1") (pintype "passive"))
      (node (ref "SW1") (pin "6") (pinfunction "6_6") (pintype "passive"))
      (node (ref "SW2") (pin "3") (pinfunction "3_3") (pintype "passive"))
    )
    (net (code "102") (name "Net-(R3-Pad1)") (class "Default")
      (node (ref "R3") (pin "1") (pinfunction "1_1") (pintype "passive"))
      (node (ref "SW1") (pin "7") (pinfunction "7_7") (pintype "passive"))
      (node (ref "SW2") (pin "2") (pinfunction "2_2") (pintype "passive"))
    )
    (net (code "103") (name "Net-(R4-Pad1)") (class "Default")
      (node (ref "R4") (pin "1") (pinfunction "1_1") (pintype "passive"))
      (node (ref "SW1") (pin "8") (pinfunction "8_8") (pintype "passive"))
      (node (ref "SW2") (pin "1") (pinfunction "1_1") (pintype "passive"))
    )
    (net (code "104") (name "VDD") (class "Default")
      (node (ref "SV2") (pin "1") (pinfunction "1_1") (pintype "passive"))
      (node (ref "SW2") (pin "5") (pinfunction "5_5") (pintype "passive"))
      (node (ref "SW2") (pin "6") (pinfunction "6_6") (pintype "passive"))
      (node (ref "SW2") (pin "7") (pinfunction "7_7") (pintype "passive"))
      (node (ref "SW2") (pin "8") (pinfunction "8_8") (pintype "passive"))
    )
    (net (code "105") (name "unconnected-(IC18C-I1-Pad9)") (class "Default")
      (node (ref "IC18") (pin "9") (pinfunction "I1_9") (pintype "input"))
    )
    (net (code "106") (name "unconnected-(SV2-Pad3)") (class "Default")
      (node (ref "SV2") (pin "3") (pinfunction "3_3") (pintype "passive"))
    )
  )
)
